# periph.net
KiCad netlist of a schematic drawn in Altium Designer
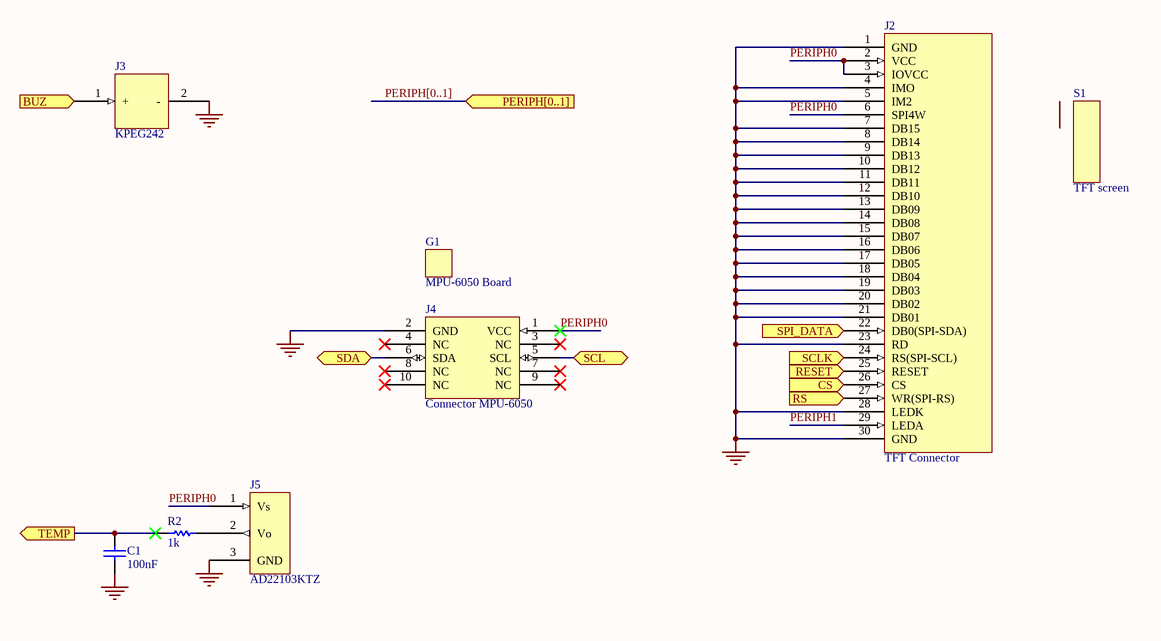
[diagram p0: periph.SchDoc]

(export (version "E")
  (design (tool "Eeschema 10.0.6"))
  (components
    (comp (ref "C1")
      (value "100nF")
      (footprint "CAPACITOR")
      (description "Capacitor")
      (fields (field (name "PUBLISHER") "Altium Limited"))
      (libsource (lib "Miscellaneous Devices") (part "Cap"))
    )
    (comp (ref "G1") (value "MPU-6050 Board") (libsource (lib "Klotz") (part "MPU-6050")))
    (comp (ref "J2")
      (value "TFT Connector")
      (footprint "SCREEN")
      (libsource (lib "Klotz") (part "MCT0144C6W128128PML"))
    )
    (comp (ref "J3")
      (value "KPEG242")
      (footprint "BUZZER")
      (description "Buzzer")
      (libsource (lib "Klotz") (part "KPEG242"))
    )
    (comp (ref "J4")
      (value "Connector MPU-6050")
      (footprint "GYROSCOPE")
      (libsource (lib "Klotz") (part "Connector MPU-6050"))
    )
    (comp (ref "J5")
      (value "AD22103KTZ")
      (footprint "TEMP")
      (description "Temp sensor")
      (libsource (lib "Klotz") (part "AD22103KTZ"))
    )
    (comp (ref "R2")
      (value "1k")
      (footprint "Resistor")
      (description "Resistor")
      (fields (field (name "PUBLISHER") "Altium Limited"))
      (libsource (lib "Miscellaneous Devices") (part "Res1"))
    )
    (comp (ref "S1") (value "TFT screen") (libsource (lib "Klotz") (part "Connector display")))
  )
  (nets
    (net (code "1") (name "/BUZ") (class "Default")
      (node (ref "J3") (pin "1") (pinfunction "+_1") (pintype "input"))
    )
    (net (code "2") (name "/CS") (class "Default")
      (node (ref "J2") (pin "26") (pinfunction "CS_26") (pintype "input"))
    )
    (net (code "3") (name "/PERIPH0") (class "Default")
      (node (ref "J2") (pin "2") (pinfunction "VCC_2") (pintype "input"))
      (node (ref "J2") (pin "3") (pinfunction "IOVCC_3") (pintype "input"))
      (node (ref "J2") (pin "6") (pinfunction "SPI4W_6") (pintype "power_in"))
      (node (ref "J4") (pin "1") (pinfunction "VCC_1") (pintype "input"))
      (node (ref "J5") (pin "1") (pinfunction "Vs_1") (pintype "input"))
    )
    (net (code "4") (name "/PERIPH1") (class "Default")
      (node (ref "J2") (pin "29") (pinfunction "LEDA_29") (pintype "input"))
    )
    (net (code "6") (name "/RESET") (class "Default")
      (node (ref "J2") (pin "25") (pinfunction "RESET_25") (pintype "input"))
    )
    (net (code "7") (name "/RS") (class "Default")
      (node (ref "J2") (pin "27") (pinfunction "WR(SPI-RS)_27") (pintype "input"))
    )
    (net (code "8") (name "/SCL") (class "Default")
      (node (ref "J4") (pin "5") (pinfunction "SCL_5") (pintype "bidirectional"))
    )
    (net (code "9") (name "/SCLK") (class "Default")
      (node (ref "J2") (pin "24") (pinfunction "RS(SPI-SCL)_24") (pintype "input"))
    )
    (net (code "10") (name "/SDA") (class "Default")
      (node (ref "J4") (pin "6") (pinfunction "SDA_6") (pintype "bidirectional"))
    )
    (net (code "11") (name "/SPI_DATA") (class "Default")
      (node (ref "J2") (pin "22") (pinfunction "DB0(SPI-SDA)_22") (pintype "input"))
    )
    (net (code "12") (name "/TEMP") (class "Default")
      (node (ref "C1") (pin "2") (pinfunction "2_2") (pintype "passive"))
      (node (ref "R2") (pin "2") (pinfunction "2_2") (pintype "passive"))
    )
    (net (code "13") (name "GND") (class "Default")
      (node (ref "C1") (pin "1") (pinfunction "1_1") (pintype "passive"))
      (node (ref "J2") (pin "1") (pinfunction "GND_1") (pintype "power_in"))
      (node (ref "J2") (pin "10") (pinfunction "DB12_10") (pintype "power_in"))
      (node (ref "J2") (pin "11") (pinfunction "DB11_11") (pintype "power_in"))
      (node (ref "J2") (pin "12") (pinfunction "DB10_12") (pintype "power_in"))
      (node (ref "J2") (pin "13") (pinfunction "DB09_13") (pintype "power_in"))
      (node (ref "J2") (pin "14") (pinfunction "DB08_14") (pintype "power_in"))
      (node (ref "J2") (pin "15") (pinfunction "DB07_15") (pintype "power_in"))
      (node (ref "J2") (pin "16") (pinfunction "DB06_16") (pintype "power_in"))
      (node (ref "J2") (pin "17") (pinfunction "DB05_17") (pintype "power_in"))
      (node (ref "J2") (pin "18") (pinfunction "DB04_18") (pintype "power_in"))
      (node (ref "J2") (pin "19") (pinfunction "DB03_19") (pintype "power_in"))
      (node (ref "J2") (pin "20") (pinfunction "DB02_20") (pintype "power_in"))
      (node (ref "J2") (pin "21") (pinfunction "DB01_21") (pintype "power_in"))
      (node (ref "J2") (pin "23") (pinfunction "RD_23") (pintype "power_in"))
      (node (ref "J2") (pin "28") (pinfunction "LEDK_28") (pintype "power_in"))
      (node (ref "J2") (pin "30") (pinfunction "GND_30") (pintype "power_in"))
      (node (ref "J2") (pin "4") (pinfunction "IMO_4") (pintype "power_in"))
      (node (ref "J2") (pin "5") (pinfunction "IM2_5") (pintype "power_in"))
      (node (ref "J2") (pin "7") (pinfunction "DB15_7") (pintype "power_in"))
      (node (ref "J2") (pin "8") (pinfunction "DB14_8") (pintype "power_in"))
      (node (ref "J2") (pin "9") (pinfunction "DB13_9") (pintype "power_in"))
      (node (ref "J3") (pin "2") (pinfunction "-_2") (pintype "power_in"))
      (node (ref "J4") (pin "2") (pinfunction "GND_2") (pintype "passive"))
      (node (ref "J5") (pin "3") (pinfunction "GND_3") (pintype "power_in"))
    )
    (net (code "14") (name "Net-(J5-Vo)") (class "Default")
      (node (ref "J5") (pin "2") (pinfunction "Vo_2") (pintype "output"))
      (node (ref "R2") (pin "1") (pinfunction "1_1") (pintype "passive"))
    )
    (net (code "15") (name "unconnected-(J4-NC-Pad3)") (class "Default")
      (node (ref "J4") (pin "3") (pinfunction "NC_3") (pintype "passive+no_connect"))
    )
    (net (code "16") (name "unconnected-(J4-NC-Pad4)") (class "Default")
      (node (ref "J4") (pin "4") (pinfunction "NC_4") (pintype "passive+no_connect"))
    )
    (net (code "17") (name "unconnected-(J4-NC-Pad7)") (class "Default")
      (node (ref "J4") (pin "7") (pinfunction "NC_7") (pintype "passive+no_connect"))
    )
    (net (code "18") (name "unconnected-(J4-NC-Pad8)") (class "Default")
      (node (ref "J4") (pin "8") (pinfunction "NC_8") (pintype "passive+no_connect"))
    )
    (net (code "19") (name "unconnected-(J4-NC-Pad9)") (class "Default")
      (node (ref "J4") (pin "9") (pinfunction "NC_9") (pintype "passive+no_connect"))
    )
    (net (code "20") (name "unconnected-(J4-NC-Pad10)") (class "Default")
      (node (ref "J4") (pin "10") (pinfunction "NC_10") (pintype "passive+no_connect"))
    )
  )
)
